# figro.net
KiCad netlist of a schematic drawn in EAGLE
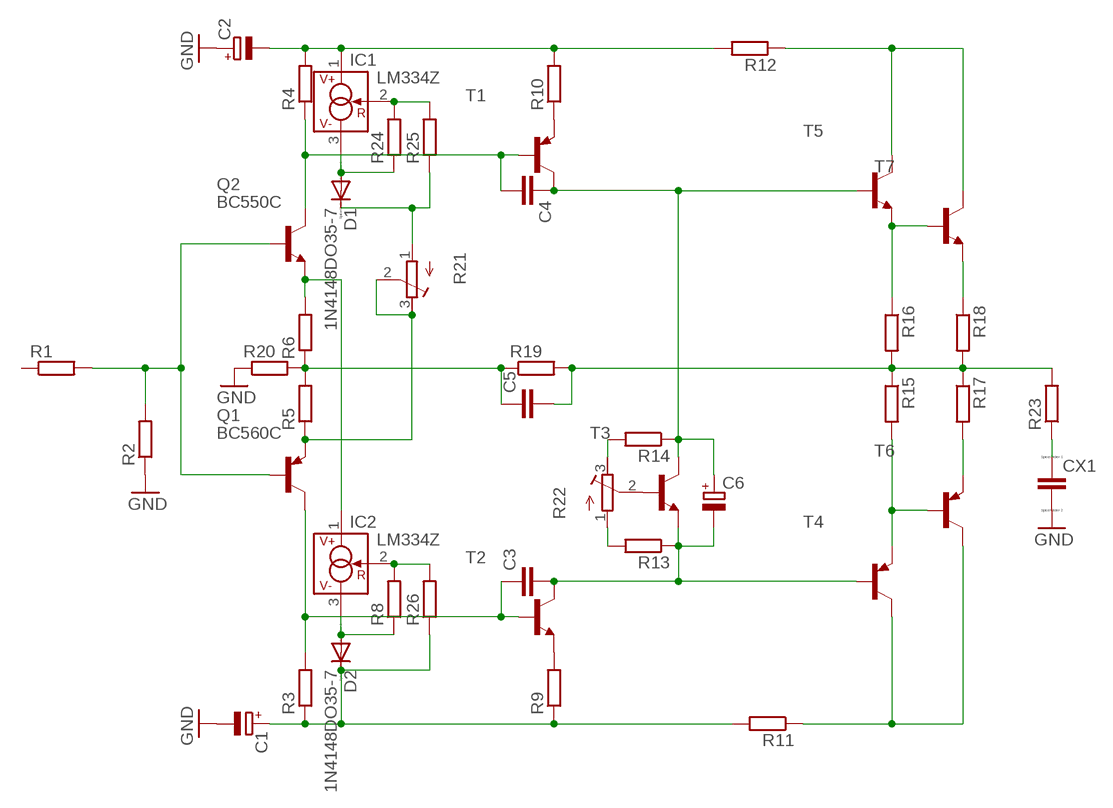
[diagram p0: schematic, sheet 1]

(export (version "E")
  (design (tool "Eeschema 10.0.6"))
  (components
    (comp (ref "C1")
      (value "CPOL-EUE7.5-18")
      (footprint "eagle-import:E7,5-18")
      (libsource (lib "eagle-import") (part "CPOL-EUE7.5-18"))
    )
    (comp (ref "C2")
      (value "CPOL-EUE7.5-18")
      (footprint "eagle-import:E7,5-18")
      (libsource (lib "eagle-import") (part "CPOL-EUE7.5-18"))
    )
    (comp (ref "C3")
      (value "C-EU050-030X075")
      (footprint "eagle-import:C050-030X075")
      (libsource (lib "eagle-import") (part "C-EU050-030X075"))
    )
    (comp (ref "C4")
      (value "C-EU050-030X075")
      (footprint "eagle-import:C050-030X075")
      (libsource (lib "eagle-import") (part "C-EU050-030X075"))
    )
    (comp (ref "C5")
      (value "C-EU050-030X075")
      (footprint "eagle-import:C050-030X075")
      (libsource (lib "eagle-import") (part "C-EU050-030X075"))
    )
    (comp (ref "C6")
      (value "CPOL-EUE2.5-7")
      (footprint "eagle-import:E2,5-7")
      (libsource (lib "eagle-import") (part "CPOL-EUE2.5-7"))
    )
    (comp (ref "CX1")
      (value "CXXC15B6")
      (footprint "eagle-import:XC15B6")
      (libsource (lib "eagle-import") (part "CXXC15B6"))
    )
    (comp (ref "D1")
      (value "1N4148DO35-7")
      (footprint "eagle-import:DO35-7")
      (libsource (lib "eagle-import") (part "1N4148DO35-7"))
    )
    (comp (ref "D2")
      (value "1N4148DO35-7")
      (footprint "eagle-import:DO35-7")
      (libsource (lib "eagle-import") (part "1N4148DO35-7"))
    )
    (comp (ref "IC1")
      (value "LM334Z")
      (footprint "eagle-import:TO92")
      (libsource (lib "eagle-import") (part "LM34Z3"))
    )
    (comp (ref "IC2")
      (value "LM334Z")
      (footprint "eagle-import:TO92")
      (libsource (lib "eagle-import") (part "LM34Z3"))
    )
    (comp (ref "Q1")
      (value "BC560C")
      (footprint "eagle-import:TO92-EBC")
      (libsource (lib "eagle-import") (part "BC560C"))
    )
    (comp (ref "Q2")
      (value "BC550C")
      (footprint "eagle-import:TO92-EBC")
      (libsource (lib "eagle-import") (part "BC550C"))
    )
    (comp (ref "R1")
      (value "R-EU_0207/10")
      (footprint "eagle-import:0207_10")
      (libsource (lib "eagle-import") (part "R-EU_0207/10"))
    )
    (comp (ref "R2")
      (value "R-EU_0207/10")
      (footprint "eagle-import:0207_10")
      (libsource (lib "eagle-import") (part "R-EU_0207/10"))
    )
    (comp (ref "R3")
      (value "R-EU_0207/10")
      (footprint "eagle-import:0207_10")
      (libsource (lib "eagle-import") (part "R-EU_0207/10"))
    )
    (comp (ref "R4")
      (value "R-EU_0207/10")
      (footprint "eagle-import:0207_10")
      (libsource (lib "eagle-import") (part "R-EU_0207/10"))
    )
    (comp (ref "R5")
      (value "R-EU_0207/10")
      (footprint "eagle-import:0207_10")
      (libsource (lib "eagle-import") (part "R-EU_0207/10"))
    )
    (comp (ref "R6")
      (value "R-EU_0207/10")
      (footprint "eagle-import:0207_10")
      (libsource (lib "eagle-import") (part "R-EU_0207/10"))
    )
    (comp (ref "R8")
      (value "R-EU_0207/10")
      (footprint "eagle-import:0207_10")
      (libsource (lib "eagle-import") (part "R-EU_0207/10"))
    )
    (comp (ref "R9")
      (value "R-EU_0207/10")
      (footprint "eagle-import:0207_10")
      (libsource (lib "eagle-import") (part "R-EU_0207/10"))
    )
    (comp (ref "R10")
      (value "R-EU_0207/10")
      (footprint "eagle-import:0207_10")
      (libsource (lib "eagle-import") (part "R-EU_0207/10"))
    )
    (comp (ref "R11")
      (value "R-EU_0207/10")
      (footprint "eagle-import:0207_10")
      (libsource (lib "eagle-import") (part "R-EU_0207/10"))
    )
    (comp (ref "R12")
      (value "R-EU_0207/10")
      (footprint "eagle-import:0207_10")
      (libsource (lib "eagle-import") (part "R-EU_0207/10"))
    )
    (comp (ref "R13")
      (value "R-EU_0207/10")
      (footprint "eagle-import:0207_10")
      (libsource (lib "eagle-import") (part "R-EU_0207/10"))
    )
    (comp (ref "R14")
      (value "R-EU_0207/10")
      (footprint "eagle-import:0207_10")
      (libsource (lib "eagle-import") (part "R-EU_0207/10"))
    )
    (comp (ref "R15")
      (value "R-EU_0207/10")
      (footprint "eagle-import:0207_10")
      (libsource (lib "eagle-import") (part "R-EU_0207/10"))
    )
    (comp (ref "R16")
      (value "R-EU_0207/10")
      (footprint "eagle-import:0207_10")
      (libsource (lib "eagle-import") (part "R-EU_0207/10"))
    )
    (comp (ref "R17")
      (value "R-EU_0309/12")
      (footprint "eagle-import:0309_12")
      (libsource (lib "eagle-import") (part "R-EU_0309/12"))
    )
    (comp (ref "R18")
      (value "R-EU_0309/12")
      (footprint "eagle-import:0309_12")
      (libsource (lib "eagle-import") (part "R-EU_0309/12"))
    )
    (comp (ref "R19")
      (value "R-EU_0207/10")
      (footprint "eagle-import:0207_10")
      (libsource (lib "eagle-import") (part "R-EU_0207/10"))
    )
    (comp (ref "R20")
      (value "R-EU_0207/10")
      (footprint "eagle-import:0207_10")
      (libsource (lib "eagle-import") (part "R-EU_0207/10"))
    )
    (comp (ref "R21")
      (value "R-TRIMM64W")
      (footprint "eagle-import:RTRIM64W")
      (libsource (lib "eagle-import") (part "R-TRIMM64W"))
    )
    (comp (ref "R22")
      (value "R-TRIMM64W")
      (footprint "eagle-import:RTRIM64W")
      (libsource (lib "eagle-import") (part "R-TRIMM64W"))
    )
    (comp (ref "R23")
      (value "R-EU_0309/12")
      (footprint "eagle-import:0309_12")
      (libsource (lib "eagle-import") (part "R-EU_0309/12"))
    )
    (comp (ref "R24")
      (value "R-EU_0207/10")
      (footprint "eagle-import:0207_10")
      (libsource (lib "eagle-import") (part "R-EU_0207/10"))
    )
    (comp (ref "R25")
      (value "R-EU_0207/10")
      (footprint "eagle-import:0207_10")
      (libsource (lib "eagle-import") (part "R-EU_0207/10"))
    )
    (comp (ref "R26")
      (value "R-EU_0207/10")
      (footprint "eagle-import:0207_10")
      (libsource (lib "eagle-import") (part "R-EU_0207/10"))
    )
    (comp (ref "T1")
      (value "MPSA56-PNP-TO92-BCE")
      (footprint "eagle-import:TO92-BCE")
      (libsource (lib "eagle-import") (part "-PNP-TO92-BCEMPSA56"))
    )
    (comp (ref "T2")
      (value "MPSA06-NPN-TO92-EBC")
      (footprint "eagle-import:TO92-EBC")
      (libsource (lib "eagle-import") (part "-NPN-TO92-EBCMPSA06"))
    )
    (comp (ref "T3")
      (value "-NPN-TO126V")
      (footprint "eagle-import:TO126V")
      (libsource (lib "eagle-import") (part "transistor-neu-to92_-NPN-TO126V"))
    )
    (comp (ref "T4")
      (value "-PNP-TO220V")
      (footprint "eagle-import:TO220V")
      (libsource (lib "eagle-import") (part "transistor-neu-to92_-PNP-TO220V"))
    )
    (comp (ref "T5")
      (value "-NPN-TO220V")
      (footprint "eagle-import:TO220V")
      (libsource (lib "eagle-import") (part "transistor-neu-to92_-NPN-TO220V"))
    )
    (comp (ref "T6")
      (value "-PNP-TOP3V")
      (footprint "eagle-import:TOP3V")
      (libsource (lib "eagle-import") (part "transistor-neu-to92_-PNP-TOP3V"))
    )
    (comp (ref "T7")
      (value "-NPN-TOP3V")
      (footprint "eagle-import:TOP3V")
      (libsource (lib "eagle-import") (part "transistor-neu-to92_-NPN-TOP3V"))
    )
  )
  (nets
    (net (code "1") (name "GND") (class "Default")
      (node (ref "C1") (pin "-") (pinfunction "-_-") (pintype "passive"))
      (node (ref "C2") (pin "+") (pinfunction "+_+") (pintype "passive"))
      (node (ref "CX1") (pin "2") (pinfunction "2_2") (pintype "passive"))
      (node (ref "R2") (pin "1") (pinfunction "1_1") (pintype "passive"))
      (node (ref "R20") (pin "1") (pinfunction "1_1") (pintype "passive"))
    )
    (net (code "2") (name "Net-(C1-Pad+)") (class "Default")
      (node (ref "C1") (pin "+") (pinfunction "+_+") (pintype "passive"))
      (node (ref "D2") (pin "C") (pinfunction "C_C") (pintype "passive"))
      (node (ref "R11") (pin "2") (pinfunction "2_2") (pintype "passive"))
      (node (ref "R26") (pin "1") (pinfunction "1_1") (pintype "passive"))
      (node (ref "R3") (pin "1") (pinfunction "1_1") (pintype "passive"))
      (node (ref "R9") (pin "1") (pinfunction "1_1") (pintype "passive"))
    )
    (net (code "3") (name "Net-(C3-Pad1)") (class "Default")
      (node (ref "C3") (pin "1") (pinfunction "1_1") (pintype "passive"))
      (node (ref "Q1") (pin "C") (pinfunction "C_C") (pintype "passive"))
      (node (ref "R3") (pin "2") (pinfunction "2_2") (pintype "passive"))
      (node (ref "T2") (pin "B") (pinfunction "B_B") (pintype "passive"))
    )
    (net (code "4") (name "Net-(C4-Pad2)") (class "Default")
      (node (ref "C4") (pin "2") (pinfunction "2_2") (pintype "passive"))
      (node (ref "Q2") (pin "C") (pinfunction "C_C") (pintype "passive"))
      (node (ref "R4") (pin "1") (pinfunction "1_1") (pintype "passive"))
      (node (ref "T1") (pin "B") (pinfunction "B_B") (pintype "passive"))
    )
    (net (code "5") (name "Net-(C5-Pad1)") (class "Default")
      (node (ref "C5") (pin "1") (pinfunction "1_1") (pintype "passive"))
      (node (ref "R19") (pin "1") (pinfunction "1_1") (pintype "passive"))
      (node (ref "R20") (pin "2") (pinfunction "2_2") (pintype "passive"))
      (node (ref "R5") (pin "2") (pinfunction "2_2") (pintype "passive"))
      (node (ref "R6") (pin "1") (pinfunction "1_1") (pintype "passive"))
    )
    (net (code "6") (name "Net-(C5-Pad2)") (class "Default")
      (node (ref "C5") (pin "2") (pinfunction "2_2") (pintype "passive"))
      (node (ref "R15") (pin "1") (pinfunction "1_1") (pintype "passive"))
      (node (ref "R16") (pin "2") (pinfunction "2_2") (pintype "passive"))
      (node (ref "R17") (pin "1") (pinfunction "1_1") (pintype "passive"))
      (node (ref "R18") (pin "2") (pinfunction "2_2") (pintype "passive"))
      (node (ref "R19") (pin "2") (pinfunction "2_2") (pintype "passive"))
      (node (ref "R23") (pin "2") (pinfunction "2_2") (pintype "passive"))
    )
    (net (code "7") (name "Net-(CX1-Pad1)") (class "Default")
      (node (ref "CX1") (pin "1") (pinfunction "1_1") (pintype "passive"))
      (node (ref "R23") (pin "1") (pinfunction "1_1") (pintype "passive"))
    )
    (net (code "8") (name "Net-(IC1-R)") (class "Default")
      (node (ref "IC1") (pin "2") (pinfunction "R_2") (pintype "passive"))
      (node (ref "R24") (pin "2") (pinfunction "2_2") (pintype "passive"))
      (node (ref "R25") (pin "2") (pinfunction "2_2") (pintype "passive"))
    )
    (net (code "9") (name "Net-(IC1-V+)") (class "Default")
      (node (ref "C2") (pin "-") (pinfunction "-_-") (pintype "passive"))
      (node (ref "IC1") (pin "1") (pinfunction "V+_1") (pintype "passive"))
      (node (ref "R10") (pin "2") (pinfunction "2_2") (pintype "passive"))
      (node (ref "R12") (pin "2") (pinfunction "2_2") (pintype "passive"))
      (node (ref "R4") (pin "2") (pinfunction "2_2") (pintype "passive"))
    )
    (net (code "10") (name "Net-(IC1-V-)") (class "Default")
      (node (ref "D1") (pin "A") (pinfunction "A_A") (pintype "passive"))
      (node (ref "IC1") (pin "3") (pinfunction "V-_3") (pintype "passive"))
      (node (ref "R24") (pin "1") (pinfunction "1_1") (pintype "passive"))
    )
    (net (code "11") (name "Net-(IC2-R)") (class "Default")
      (node (ref "IC2") (pin "2") (pinfunction "R_2") (pintype "passive"))
      (node (ref "R26") (pin "2") (pinfunction "2_2") (pintype "passive"))
      (node (ref "R8") (pin "2") (pinfunction "2_2") (pintype "passive"))
    )
    (net (code "12") (name "Net-(IC2-V+)") (class "Default")
      (node (ref "IC2") (pin "1") (pinfunction "V+_1") (pintype "passive"))
      (node (ref "Q2") (pin "E") (pinfunction "E_E") (pintype "passive"))
      (node (ref "R6") (pin "2") (pinfunction "2_2") (pintype "passive"))
    )
    (net (code "13") (name "Net-(IC2-V-)") (class "Default")
      (node (ref "D2") (pin "A") (pinfunction "A_A") (pintype "passive"))
      (node (ref "IC2") (pin "3") (pinfunction "V-_3") (pintype "passive"))
      (node (ref "R8") (pin "1") (pinfunction "1_1") (pintype "passive"))
    )
    (net (code "14") (name "Net-(Q1-PadB)") (class "Default")
      (node (ref "Q1") (pin "B") (pinfunction "B_B") (pintype "passive"))
      (node (ref "Q2") (pin "B") (pinfunction "B_B") (pintype "passive"))
      (node (ref "R1") (pin "2") (pinfunction "2_2") (pintype "passive"))
      (node (ref "R2") (pin "2") (pinfunction "2_2") (pintype "passive"))
    )
    (net (code "15") (name "Net-(R9-Pad2)") (class "Default")
      (node (ref "R9") (pin "2") (pinfunction "2_2") (pintype "passive"))
      (node (ref "T2") (pin "E") (pinfunction "E_E") (pintype "passive"))
    )
    (net (code "16") (name "Net-(R10-Pad1)") (class "Default")
      (node (ref "R10") (pin "1") (pinfunction "1_1") (pintype "passive"))
      (node (ref "T1") (pin "E") (pinfunction "E_E") (pintype "passive"))
    )
    (net (code "17") (name "Net-(R17-Pad2)") (class "Default")
      (node (ref "R17") (pin "2") (pinfunction "2_2") (pintype "passive"))
      (node (ref "T6") (pin "E") (pinfunction "E_E") (pintype "passive"))
    )
    (net (code "18") (name "Net-(R18-Pad1)") (class "Default")
      (node (ref "R18") (pin "1") (pinfunction "1_1") (pintype "passive"))
      (node (ref "T7") (pin "E") (pinfunction "E_E") (pintype "passive"))
    )
    (net (code "19") (name "Net-(R21-A)") (class "Default")
      (node (ref "D1") (pin "C") (pinfunction "C_C") (pintype "passive"))
      (node (ref "R21") (pin "1") (pinfunction "A_1") (pintype "passive"))
      (node (ref "R25") (pin "1") (pinfunction "1_1") (pintype "passive"))
    )
    (net (code "20") (name "Net-(R21-E)") (class "Default")
      (node (ref "Q1") (pin "E") (pinfunction "E_E") (pintype "passive"))
      (node (ref "R21") (pin "2") (pinfunction "S_2") (pintype "passive"))
      (node (ref "R21") (pin "3") (pinfunction "E_3") (pintype "passive"))
      (node (ref "R5") (pin "1") (pinfunction "1_1") (pintype "passive"))
    )
    (net (code "21") (name "Net-(R22-A)") (class "Default")
      (node (ref "R13") (pin "2") (pinfunction "2_2") (pintype "passive"))
      (node (ref "R22") (pin "1") (pinfunction "A_1") (pintype "passive"))
    )
    (net (code "22") (name "Net-(R22-E)") (class "Default")
      (node (ref "R14") (pin "2") (pinfunction "2_2") (pintype "passive"))
      (node (ref "R22") (pin "3") (pinfunction "E_3") (pintype "passive"))
    )
    (net (code "23") (name "Net-(R22-S)") (class "Default")
      (node (ref "R22") (pin "2") (pinfunction "S_2") (pintype "passive"))
      (node (ref "T3") (pin "3") (pinfunction "B_3") (pintype "passive"))
    )
    (net (code "24") (name "Net-(T3-C)") (class "Default")
      (node (ref "C4") (pin "1") (pinfunction "1_1") (pintype "passive"))
      (node (ref "C6") (pin "+") (pinfunction "+_+") (pintype "passive"))
      (node (ref "R14") (pin "1") (pinfunction "1_1") (pintype "passive"))
      (node (ref "T1") (pin "C") (pinfunction "C_C") (pintype "passive"))
      (node (ref "T3") (pin "2") (pinfunction "C_2") (pintype "passive"))
      (node (ref "T5") (pin "1") (pinfunction "B_1") (pintype "passive"))
    )
    (net (code "25") (name "Net-(T3-E)") (class "Default")
      (node (ref "C3") (pin "2") (pinfunction "2_2") (pintype "passive"))
      (node (ref "C6") (pin "-") (pinfunction "-_-") (pintype "passive"))
      (node (ref "R13") (pin "1") (pinfunction "1_1") (pintype "passive"))
      (node (ref "T2") (pin "C") (pinfunction "C_C") (pintype "passive"))
      (node (ref "T3") (pin "1") (pinfunction "E_1") (pintype "passive"))
      (node (ref "T4") (pin "1") (pinfunction "B_1") (pintype "passive"))
    )
    (net (code "26") (name "Net-(T4-C)") (class "Default")
      (node (ref "R11") (pin "1") (pinfunction "1_1") (pintype "passive"))
      (node (ref "T4") (pin "2") (pinfunction "C_2") (pintype "passive"))
      (node (ref "T6") (pin "C") (pinfunction "C_C") (pintype "passive"))
    )
    (net (code "27") (name "Net-(T4-E)") (class "Default")
      (node (ref "R15") (pin "2") (pinfunction "2_2") (pintype "passive"))
      (node (ref "T4") (pin "3") (pinfunction "E_3") (pintype "passive"))
      (node (ref "T6") (pin "B") (pinfunction "B_B") (pintype "passive"))
    )
    (net (code "28") (name "Net-(T5-C)") (class "Default")
      (node (ref "R12") (pin "1") (pinfunction "1_1") (pintype "passive"))
      (node (ref "T5") (pin "2") (pinfunction "C_2") (pintype "passive"))
      (node (ref "T7") (pin "C") (pinfunction "C_C") (pintype "passive"))
    )
    (net (code "29") (name "Net-(T5-E)") (class "Default")
      (node (ref "R16") (pin "1") (pinfunction "1_1") (pintype "passive"))
      (node (ref "T5") (pin "3") (pinfunction "E_3") (pintype "passive"))
      (node (ref "T7") (pin "B") (pinfunction "B_B") (pintype "passive"))
    )
    (net (code "30") (name "unconnected-(R1-Pad1)") (class "Default")
      (node (ref "R1") (pin "1") (pinfunction "1_1") (pintype "passive"))
    )
  )
)
